# TPIC6B595_CommunicationInterface.net
KiCad netlist of a schematic drawn in Altium Designer
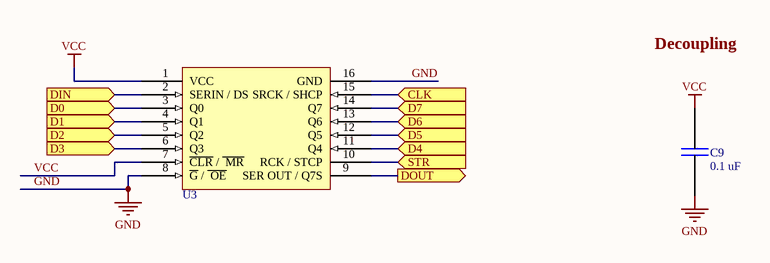
[diagram p0: TPIC6B595_CommunicationInterface.SchDoc]

(export (version "E")
  (design (tool "Eeschema 10.0.6"))
  (components
    (comp (ref "C9")
      (value "0.1 uF")
      (footprint "techdev:CAP0603")
      (description "Capacitores cerámicos de capas múltiples (MLCC) - SMD/SMT 0603 0.1uF 16volts X7R 5%")
      (fields (field (name "MPN") "VJ0603Y104JXJPW1BC") (field (name "Comment") "CAP0.1uF"))
      (libsource (lib "Miscellaneous Devices") (part "C0.1UF"))
    )
    (comp (ref "U3")
      (value "POWER SHIFT REG")
      (footprint "NPIC6C595_Q100_SOIC16")
      (description "Registros de cambio de contadores 8bit Shift")
      (fields (field (name "MPN") "NPIC6C595D-Q100"))
      (libsource (lib "Miscellaneous Devices") (part "TPIC6C595DR / NPIC6C595D"))
    )
  )
  (nets
    (net (code "1") (name "/CLK") (class "Default")
      (node (ref "U3") (pin "15") (pinfunction "SRCK_/_SHCP_15") (pintype "input"))
    )
    (net (code "2") (name "/D0") (class "Default")
      (node (ref "U3") (pin "3") (pinfunction "Q0_3") (pintype "input"))
    )
    (net (code "3") (name "/D1") (class "Default")
      (node (ref "U3") (pin "4") (pinfunction "Q1_4") (pintype "input"))
    )
    (net (code "4") (name "/D2") (class "Default")
      (node (ref "U3") (pin "5") (pinfunction "Q2_5") (pintype "input"))
    )
    (net (code "5") (name "/D3") (class "Default")
      (node (ref "U3") (pin "6") (pinfunction "Q3_6") (pintype "input"))
    )
    (net (code "6") (name "/D4") (class "Default")
      (node (ref "U3") (pin "11") (pinfunction "Q4_11") (pintype "input"))
    )
    (net (code "7") (name "/D5") (class "Default")
      (node (ref "U3") (pin "12") (pinfunction "Q5_12") (pintype "input"))
    )
    (net (code "8") (name "/D6") (class "Default")
      (node (ref "U3") (pin "13") (pinfunction "Q6_13") (pintype "input"))
    )
    (net (code "9") (name "/D7") (class "Default")
      (node (ref "U3") (pin "14") (pinfunction "Q7_14") (pintype "input"))
    )
    (net (code "10") (name "/DIN") (class "Default")
      (node (ref "U3") (pin "2") (pinfunction "SERIN_/_DS_2") (pintype "input"))
    )
    (net (code "11") (name "/DOUT") (class "Default")
      (node (ref "U3") (pin "9") (pinfunction "SER_OUT_/_Q7S_9") (pintype "passive"))
    )
    (net (code "13") (name "/STR") (class "Default")
      (node (ref "U3") (pin "10") (pinfunction "RCK_/_STCP_10") (pintype "passive"))
    )
    (net (code "14") (name "GND") (class "Default")
      (node (ref "C9") (pin "2") (pintype "passive"))
      (node (ref "U3") (pin "16") (pinfunction "GND_16") (pintype "passive"))
      (node (ref "U3") (pin "8") (pinfunction "~{G}_/_~{_OE}_8") (pintype "input"))
    )
    (net (code "15") (name "VCC") (class "Default")
      (node (ref "C9") (pin "1") (pintype "passive"))
      (node (ref "U3") (pin "1") (pinfunction "VCC_1") (pintype "passive"))
      (node (ref "U3") (pin "7") (pinfunction "~{CLR}_/_~{_MR}_7") (pintype "input"))
    )
  )
)
